# Power_24V.net
KiCad netlist of a schematic drawn in Altium Designer
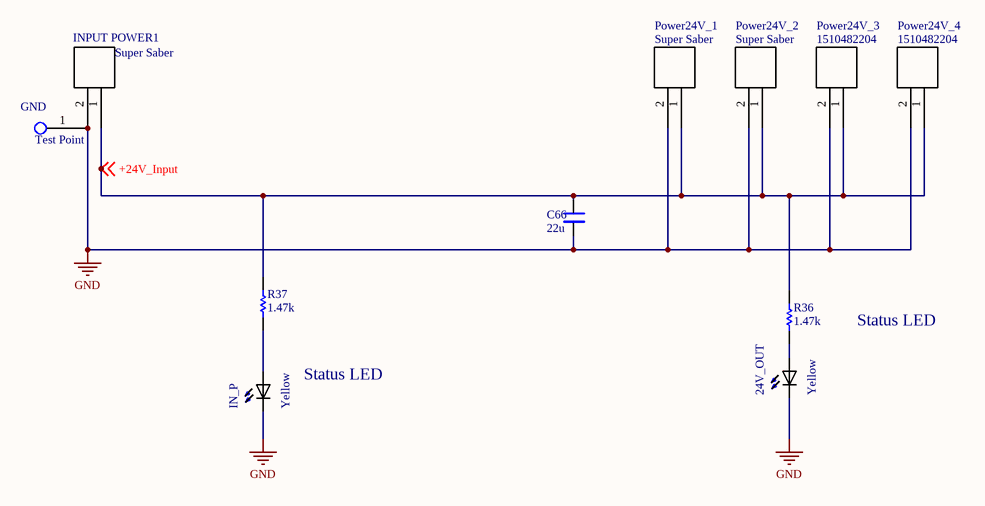
[diagram p0: Power_24V.SchDoc]

(export (version "E")
  (design (tool "Eeschema 10.0.6"))
  (components
    (comp (ref "24V_OUT")
      (value "Yellow")
      (footprint "*DIOC200X125X110_LTST-C171KSKT(Primary)")
      (description "Yellow 2 x 1.25 x 0.8 mm 130Â° Water Clear 50 mcd 2 V LED SMT")
      (fields (field (name "MP") "LTST-C171KSKT") (field (name "DIGI-KEY_PART_NUMBER") "160-1428-1-ND"))
      (libsource (lib "LTST-C171KSKT") (part "LTST-C171KSKT"))
    )
    (comp (ref "C66")
      (value "22u")
      (footprint "*CAPC2012X88N")
      (description "100pF Â±5% 250V Ceramic Capacitor C0G, NP0 0805 _2012 Metric_")
      (fields (field (name "MF") "KEMET") (field (name "DIGI-KEY_PART_NUMBER") "399-15000-1-ND"))
      (libsource (lib "C0805C101JAGAC7800") (part "C0805C101JAGAC7800"))
    )
    (comp (ref "GND")
      (value "Test Point")
      (footprint "Test Point Through-hole")
      (libsource (lib "Test Points") (part "Test Point"))
    )
    (comp (ref "INPUT POWER1")
      (value "Super Saber")
      (footprint "1720420202")
      (libsource (lib "Connector Schematic Symbols") (part "Super Saber"))
    )
    (comp (ref "IN_P")
      (value "Yellow")
      (footprint "*DIOC200X125X110_LTST-C171KSKT(Primary)")
      (description "Yellow 2 x 1.25 x 0.8 mm 130Â° Water Clear 50 mcd 2 V LED SMT")
      (fields (field (name "MP") "LTST-C171KSKT") (field (name "DIGI-KEY_PART_NUMBER") "160-1428-1-ND"))
      (libsource (lib "LTST-C171KSKT") (part "LTST-C171KSKT"))
    )
    (comp (ref "Power24V_1")
      (value "Super Saber")
      (footprint "1720420202")
      (libsource (lib "Connector Schematic Symbols") (part "Super Saber"))
    )
    (comp (ref "Power24V_2")
      (value "Super Saber")
      (footprint "1720420202")
      (libsource (lib "Connector Schematic Symbols") (part "Super Saber"))
    )
    (comp (ref "Power24V_3")
      (value "1510482204")
      (footprint "1510482204")
      (description "Molex 6.5MM 2 pin connector, used for power connections. P/N 1510482204 and similar models.")
      (libsource (lib "Power Distribution") (part "1510482204"))
    )
    (comp (ref "Power24V_4")
      (value "1510482204")
      (footprint "1510482204")
      (description "Molex 6.5MM 2 pin connector, used for power connections. P/N 1510482204 and similar models.")
      (libsource (lib "Power Distribution") (part "1510482204"))
    )
    (comp (ref "R36")
      (value "1.47k")
      (footprint "RESC0805(2012)_M")
      (description "8M06 0.125W 1% 0805 (2012 Metric)  SMD")
      (fields (field (name "POWER") "0.125 W") (field (name "TOLERANCE") "1 %"))
      (libsource (lib "Altium Content Vault") (part "RES"))
    )
    (comp (ref "R37")
      (value "1.47k")
      (footprint "RESC0805(2012)_M")
      (description "8M06 0.125W 1% 0805 (2012 Metric)  SMD")
      (fields (field (name "POWER") "0.125 W") (field (name "TOLERANCE") "1 %"))
      (libsource (lib "Altium Content Vault") (part "RES"))
    )
  )
  (nets
    (net (code "1") (name "+24V_Input") (class "Default")
      (node (ref "C66") (pin "2") (pinfunction "2_2") (pintype "passive"))
      (node (ref "INPUT POWER1") (pin "1") (pintype "passive"))
      (node (ref "Power24V_1") (pin "1") (pintype "passive"))
      (node (ref "Power24V_2") (pin "1") (pintype "passive"))
      (node (ref "Power24V_3") (pin "1") (pintype "passive"))
      (node (ref "Power24V_4") (pin "1") (pintype "passive"))
      (node (ref "R36") (pin "2") (pinfunction "2_2") (pintype "passive"))
      (node (ref "R37") (pin "2") (pinfunction "2_2") (pintype "passive"))
    )
    (net (code "2") (name "GND") (class "Default")
      (node (ref "24V_OUT") (pin "NEG") (pinfunction "NEG_NEG") (pintype "passive"))
      (node (ref "C66") (pin "1") (pinfunction "1_1") (pintype "passive"))
      (node (ref "GND") (pin "1") (pinfunction "1_1") (pintype "passive"))
      (node (ref "INPUT POWER1") (pin "2") (pintype "passive"))
      (node (ref "IN_P") (pin "NEG") (pinfunction "NEG_NEG") (pintype "passive"))
      (node (ref "Power24V_1") (pin "2") (pintype "passive"))
      (node (ref "Power24V_2") (pin "2") (pintype "passive"))
      (node (ref "Power24V_3") (pin "2") (pintype "passive"))
      (node (ref "Power24V_4") (pin "2") (pintype "passive"))
    )
    (net (code "3") (name "Net-(24V_OUT-PadPOS)") (class "Default")
      (node (ref "24V_OUT") (pin "POS") (pinfunction "POS_POS") (pintype "passive"))
      (node (ref "R36") (pin "1") (pinfunction "1_1") (pintype "passive"))
    )
    (net (code "4") (name "Net-(IN_P-PadPOS)") (class "Default")
      (node (ref "IN_P") (pin "POS") (pinfunction "POS_POS") (pintype "passive"))
      (node (ref "R37") (pin "1") (pinfunction "1_1") (pintype "passive"))
    )
  )
)
